# Zio_4_DC_Motor_Controller.net
KiCad netlist of a schematic drawn in EAGLE
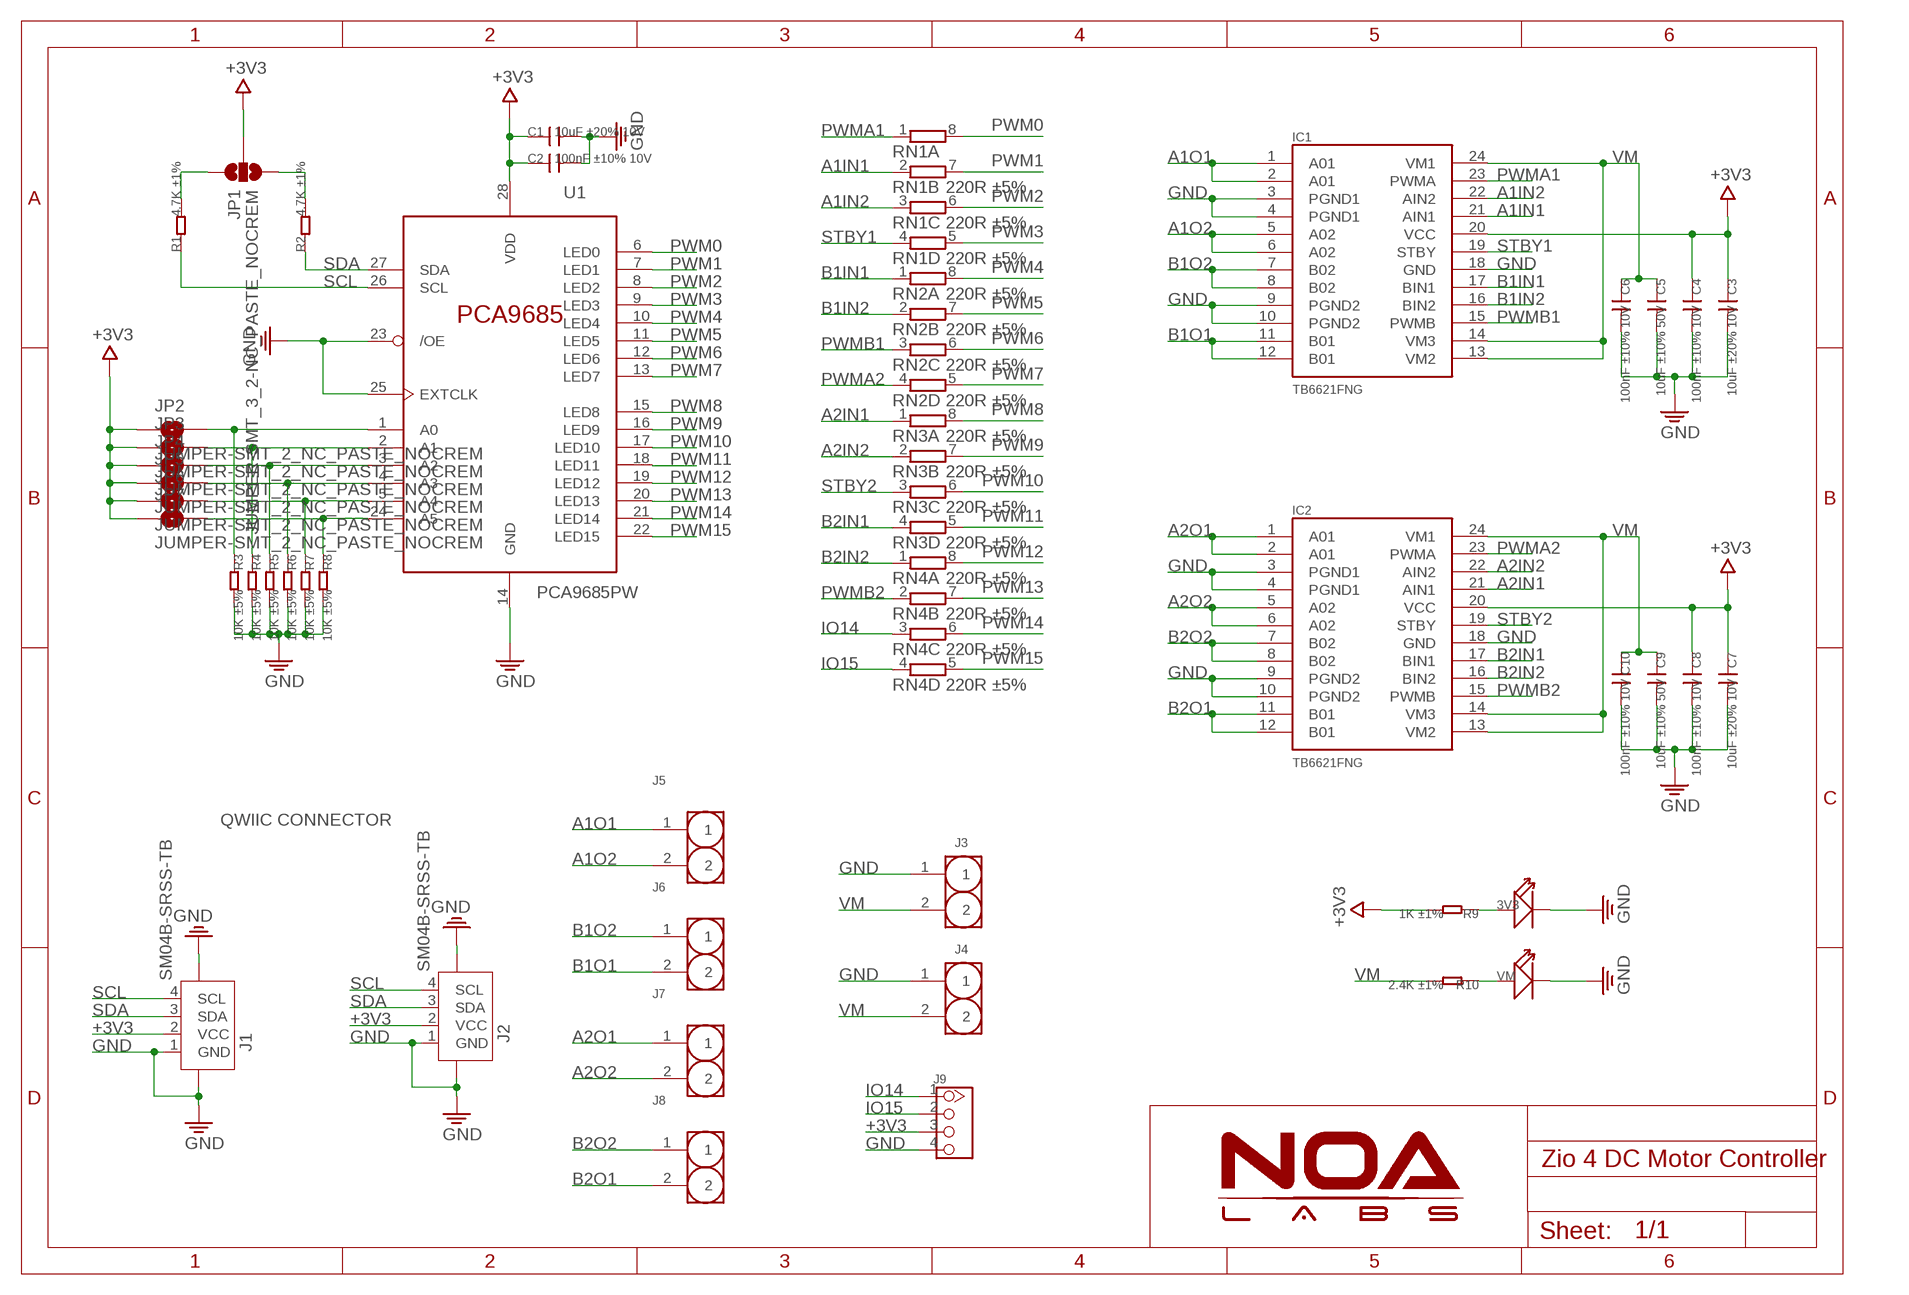
[diagram p0: schematic, sheet 1]

(export (version "E")
  (design (tool "Eeschema 10.0.6"))
  (components
    (comp (ref "3V3")
      (value "LED'0805'")
      (footprint "eagle-import:LED-0805")
      (libsource (lib "eagle-import") (part "LED'0805'"))
    )
    (comp (ref "C1")
      (value "10uF ±20% 10V")
      (footprint "eagle-import:0603")
      (libsource (lib "eagle-import") (part "C-0603"))
    )
    (comp (ref "C2")
      (value "100nF ±10% 10V")
      (footprint "eagle-import:0603")
      (libsource (lib "eagle-import") (part "C-0603"))
    )
    (comp (ref "C3")
      (value "10uF ±20% 10V")
      (footprint "eagle-import:0603")
      (libsource (lib "eagle-import") (part "C-0603"))
    )
    (comp (ref "C4")
      (value "100nF ±10% 10V")
      (footprint "eagle-import:0603")
      (libsource (lib "eagle-import") (part "C-0603"))
    )
    (comp (ref "C5")
      (value "10uF ±10% 50V")
      (footprint "eagle-import:0805")
      (libsource (lib "eagle-import") (part "C-0805"))
    )
    (comp (ref "C6")
      (value "100nF ±10% 10V")
      (footprint "eagle-import:0603")
      (libsource (lib "eagle-import") (part "C-0603"))
    )
    (comp (ref "C7")
      (value "10uF ±20% 10V")
      (footprint "eagle-import:0603")
      (libsource (lib "eagle-import") (part "C-0603"))
    )
    (comp (ref "C8")
      (value "100nF ±10% 10V")
      (footprint "eagle-import:0603")
      (libsource (lib "eagle-import") (part "C-0603"))
    )
    (comp (ref "C9")
      (value "10uF ±10% 50V")
      (footprint "eagle-import:0805")
      (libsource (lib "eagle-import") (part "C-0805"))
    )
    (comp (ref "C10")
      (value "100nF ±10% 10V")
      (footprint "eagle-import:0603")
      (libsource (lib "eagle-import") (part "C-0603"))
    )
    (comp (ref "IC1")
      (value "TB6621FNG")
      (footprint "eagle-import:SSOP24")
      (libsource (lib "eagle-import") (part "TB6621FNG"))
    )
    (comp (ref "IC2")
      (value "TB6621FNG")
      (footprint "eagle-import:SSOP24")
      (libsource (lib "eagle-import") (part "TB6621FNG"))
    )
    (comp (ref "J1")
      (value "SM04B-SRSS-TB")
      (footprint "eagle-import:JST-SH-4P")
      (libsource (lib "eagle-import") (part "JST-SH-4P-1.0"))
    )
    (comp (ref "J2")
      (value "SM04B-SRSS-TB")
      (footprint "eagle-import:JST-SH-4P")
      (libsource (lib "eagle-import") (part "JST-SH-4P-1.0"))
    )
    (comp (ref "J3")
      (value "HEADER-2P-2.0-90")
      (footprint "eagle-import:PH2.0-2P-90")
      (libsource (lib "eagle-import") (part "HEADER-2P-2.0-90"))
    )
    (comp (ref "J4")
      (value "HEADER-2P-2.0-90")
      (footprint "eagle-import:PH2.0-2P-90")
      (libsource (lib "eagle-import") (part "HEADER-2P-2.0-90"))
    )
    (comp (ref "J5")
      (value "HEADER-2P-SCREW5.0")
      (footprint "eagle-import:2P-SCREW-5.0")
      (libsource (lib "eagle-import") (part "HEADER-2P-SCREW5.0"))
    )
    (comp (ref "J6")
      (value "HEADER-2P-SCREW5.0")
      (footprint "eagle-import:2P-SCREW-5.0")
      (libsource (lib "eagle-import") (part "HEADER-2P-SCREW5.0"))
    )
    (comp (ref "J7")
      (value "HEADER-2P-SCREW5.0")
      (footprint "eagle-import:2P-SCREW-5.0")
      (libsource (lib "eagle-import") (part "HEADER-2P-SCREW5.0"))
    )
    (comp (ref "J8")
      (value "HEADER-2P-SCREW5.0")
      (footprint "eagle-import:2P-SCREW-5.0")
      (libsource (lib "eagle-import") (part "HEADER-2P-SCREW5.0"))
    )
    (comp (ref "J9")
      (value "HEADER-4P-80/40MIL")
      (footprint "eagle-import:4P-2.54-80_40MIL")
      (libsource (lib "eagle-import") (part "HEADER-4P-80/40MIL"))
    )
    (comp (ref "JP1")
      (value "JUMPER-SMT_3_2-NC_PASTE_NOCREM")
      (footprint "eagle-import:SMT-JUMPER_3_2-NC_PASTE_SILK_NOCREM")
      (libsource (lib "eagle-import") (part "JUMPER-SMT_3_2-NC_PASTE_NOCREM"))
    )
    (comp (ref "JP2")
      (value "JUMPER-SMT_2_NC_PASTE_NOCREM")
      (footprint "eagle-import:SMT-JUMPER_2_NC_PASTE_SILK_NOCREM")
      (libsource (lib "eagle-import") (part "JUMPER-SMT_2_NC_PASTE_NOCREM"))
    )
    (comp (ref "JP3")
      (value "JUMPER-SMT_2_NC_PASTE_NOCREM")
      (footprint "eagle-import:SMT-JUMPER_2_NC_PASTE_SILK_NOCREM")
      (libsource (lib "eagle-import") (part "JUMPER-SMT_2_NC_PASTE_NOCREM"))
    )
    (comp (ref "JP4")
      (value "JUMPER-SMT_2_NC_PASTE_NOCREM")
      (footprint "eagle-import:SMT-JUMPER_2_NC_PASTE_SILK_NOCREM")
      (libsource (lib "eagle-import") (part "JUMPER-SMT_2_NC_PASTE_NOCREM"))
    )
    (comp (ref "JP5")
      (value "JUMPER-SMT_2_NC_PASTE_NOCREM")
      (footprint "eagle-import:SMT-JUMPER_2_NC_PASTE_SILK_NOCREM")
      (libsource (lib "eagle-import") (part "JUMPER-SMT_2_NC_PASTE_NOCREM"))
    )
    (comp (ref "JP6")
      (value "JUMPER-SMT_2_NC_PASTE_NOCREM")
      (footprint "eagle-import:SMT-JUMPER_2_NC_PASTE_SILK_NOCREM")
      (libsource (lib "eagle-import") (part "JUMPER-SMT_2_NC_PASTE_NOCREM"))
    )
    (comp (ref "JP7")
      (value "JUMPER-SMT_2_NC_PASTE_NOCREM")
      (footprint "eagle-import:SMT-JUMPER_2_NC_PASTE_SILK_NOCREM")
      (libsource (lib "eagle-import") (part "JUMPER-SMT_2_NC_PASTE_NOCREM"))
    )
    (comp (ref "R1")
      (value "4.7K ±1%")
      (footprint "eagle-import:0603")
      (libsource (lib "eagle-import") (part "Discretex_R-0603"))
    )
    (comp (ref "R2")
      (value "4.7K ±1%")
      (footprint "eagle-import:0603")
      (libsource (lib "eagle-import") (part "Discretex_R-0603"))
    )
    (comp (ref "R3")
      (value "10K ±5%")
      (footprint "eagle-import:0402")
      (libsource (lib "eagle-import") (part "R-0402"))
    )
    (comp (ref "R4")
      (value "10K ±5%")
      (footprint "eagle-import:0402")
      (libsource (lib "eagle-import") (part "R-0402"))
    )
    (comp (ref "R5")
      (value "10K ±5%")
      (footprint "eagle-import:0402")
      (libsource (lib "eagle-import") (part "R-0402"))
    )
    (comp (ref "R6")
      (value "10K ±5%")
      (footprint "eagle-import:0402")
      (libsource (lib "eagle-import") (part "R-0402"))
    )
    (comp (ref "R7")
      (value "10K ±5%")
      (footprint "eagle-import:0402")
      (libsource (lib "eagle-import") (part "R-0402"))
    )
    (comp (ref "R8")
      (value "10K ±5%")
      (footprint "eagle-import:0402")
      (libsource (lib "eagle-import") (part "R-0402"))
    )
    (comp (ref "R9")
      (value "1K ±1%")
      (footprint "eagle-import:0603")
      (libsource (lib "eagle-import") (part "Discretex_R-0603"))
    )
    (comp (ref "R10")
      (value "2.4K ±1%")
      (footprint "eagle-import:0603")
      (libsource (lib "eagle-import") (part "Discretex_R-0603"))
    )
    (comp (ref "RN1")
      (value "220R ±5%")
      (footprint "eagle-import:RESISTOR-DIL_0603-ARV")
      (libsource (lib "eagle-import") (part "RESISTOR-DIL_4R-N0603-ARV"))
    )
    (comp (ref "RN2")
      (value "220R ±5%")
      (footprint "eagle-import:RESISTOR-DIL_0603-ARV")
      (libsource (lib "eagle-import") (part "RESISTOR-DIL_4R-N0603-ARV"))
    )
    (comp (ref "RN3")
      (value "220R ±5%")
      (footprint "eagle-import:RESISTOR-DIL_0603-ARV")
      (libsource (lib "eagle-import") (part "RESISTOR-DIL_4R-N0603-ARV"))
    )
    (comp (ref "RN4")
      (value "220R ±5%")
      (footprint "eagle-import:RESISTOR-DIL_0603-ARV")
      (libsource (lib "eagle-import") (part "RESISTOR-DIL_4R-N0603-ARV"))
    )
    (comp (ref "U1")
      (value "PCA9685PW")
      (footprint "eagle-import:TSSOP28")
      (libsource (lib "eagle-import") (part "PCA9685PW"))
    )
    (comp (ref "VM")
      (value "LED'0805'")
      (footprint "eagle-import:LED-0805")
      (libsource (lib "eagle-import") (part "LED'0805'"))
    )
  )
  (nets
    (net (code "1") (name "+3V3") (class "Default")
      (node (ref "C1") (pin "1") (pinfunction "1_1") (pintype "passive"))
      (node (ref "C2") (pin "1") (pinfunction "1_1") (pintype "passive"))
      (node (ref "C3") (pin "1") (pinfunction "1_1") (pintype "passive"))
      (node (ref "C4") (pin "1") (pinfunction "1_1") (pintype "passive"))
      (node (ref "C7") (pin "1") (pinfunction "1_1") (pintype "passive"))
      (node (ref "C8") (pin "1") (pinfunction "1_1") (pintype "passive"))
      (node (ref "IC1") (pin "20") (pinfunction "VCC_20") (pintype "bidirectional"))
      (node (ref "IC2") (pin "20") (pinfunction "VCC_20") (pintype "bidirectional"))
      (node (ref "J1") (pin "2") (pinfunction "VCC_2") (pintype "bidirectional"))
      (node (ref "J2") (pin "2") (pinfunction "VCC_2") (pintype "bidirectional"))
      (node (ref "J9") (pin "3") (pinfunction "P$3_3") (pintype "bidirectional"))
      (node (ref "JP1") (pin "2") (pinfunction "2_2") (pintype "passive"))
      (node (ref "JP2") (pin "1") (pinfunction "1_1") (pintype "passive"))
      (node (ref "JP3") (pin "1") (pinfunction "1_1") (pintype "passive"))
      (node (ref "JP4") (pin "1") (pinfunction "1_1") (pintype "passive"))
      (node (ref "JP5") (pin "1") (pinfunction "1_1") (pintype "passive"))
      (node (ref "JP6") (pin "1") (pinfunction "1_1") (pintype "passive"))
      (node (ref "JP7") (pin "1") (pinfunction "1_1") (pintype "passive"))
      (node (ref "R9") (pin "2") (pinfunction "2_2") (pintype "passive"))
      (node (ref "U1") (pin "28") (pinfunction "VDD_28") (pintype "power_in"))
    )
    (net (code "2") (name "/A1IN1") (class "Default")
      (node (ref "IC1") (pin "21") (pinfunction "AIN1_21") (pintype "bidirectional"))
      (node (ref "RN1") (pin "2") (pinfunction "1_2") (pintype "passive"))
    )
    (net (code "3") (name "/A1IN2") (class "Default")
      (node (ref "IC1") (pin "22") (pinfunction "AIN2_22") (pintype "bidirectional"))
      (node (ref "RN1") (pin "3") (pinfunction "1_3") (pintype "passive"))
    )
    (net (code "4") (name "/A1O1") (class "Default")
      (node (ref "IC1") (pin "1") (pinfunction "A01_1") (pintype "bidirectional"))
      (node (ref "IC1") (pin "2") (pinfunction "A01_2") (pintype "bidirectional"))
      (node (ref "J5") (pin "1") (pinfunction "1_1") (pintype "bidirectional"))
    )
    (net (code "5") (name "/A1O2") (class "Default")
      (node (ref "IC1") (pin "5") (pinfunction "A02_5") (pintype "bidirectional"))
      (node (ref "IC1") (pin "6") (pinfunction "A02_6") (pintype "bidirectional"))
      (node (ref "J5") (pin "2") (pinfunction "2_2") (pintype "bidirectional"))
    )
    (net (code "6") (name "/A2IN1") (class "Default")
      (node (ref "IC2") (pin "21") (pinfunction "AIN1_21") (pintype "bidirectional"))
      (node (ref "RN3") (pin "1") (pinfunction "1_1") (pintype "passive"))
    )
    (net (code "7") (name "/A2IN2") (class "Default")
      (node (ref "IC2") (pin "22") (pinfunction "AIN2_22") (pintype "bidirectional"))
      (node (ref "RN3") (pin "2") (pinfunction "1_2") (pintype "passive"))
    )
    (net (code "8") (name "/A2O1") (class "Default")
      (node (ref "IC2") (pin "1") (pinfunction "A01_1") (pintype "bidirectional"))
      (node (ref "IC2") (pin "2") (pinfunction "A01_2") (pintype "bidirectional"))
      (node (ref "J7") (pin "1") (pinfunction "1_1") (pintype "bidirectional"))
    )
    (net (code "9") (name "/A2O2") (class "Default")
      (node (ref "IC2") (pin "5") (pinfunction "A02_5") (pintype "bidirectional"))
      (node (ref "IC2") (pin "6") (pinfunction "A02_6") (pintype "bidirectional"))
      (node (ref "J7") (pin "2") (pinfunction "2_2") (pintype "bidirectional"))
    )
    (net (code "10") (name "/B1IN1") (class "Default")
      (node (ref "IC1") (pin "17") (pinfunction "BIN1_17") (pintype "bidirectional"))
      (node (ref "RN2") (pin "1") (pinfunction "1_1") (pintype "passive"))
    )
    (net (code "11") (name "/B1IN2") (class "Default")
      (node (ref "IC1") (pin "16") (pinfunction "BIN2_16") (pintype "bidirectional"))
      (node (ref "RN2") (pin "2") (pinfunction "1_2") (pintype "passive"))
    )
    (net (code "12") (name "/B1O1") (class "Default")
      (node (ref "IC1") (pin "11") (pinfunction "B01_11") (pintype "bidirectional"))
      (node (ref "IC1") (pin "12") (pinfunction "B01_12") (pintype "bidirectional"))
      (node (ref "J6") (pin "2") (pinfunction "2_2") (pintype "bidirectional"))
    )
    (net (code "13") (name "/B1O2") (class "Default")
      (node (ref "IC1") (pin "7") (pinfunction "B02_7") (pintype "bidirectional"))
      (node (ref "IC1") (pin "8") (pinfunction "B02_8") (pintype "bidirectional"))
      (node (ref "J6") (pin "1") (pinfunction "1_1") (pintype "bidirectional"))
    )
    (net (code "14") (name "/B2IN1") (class "Default")
      (node (ref "IC2") (pin "17") (pinfunction "BIN1_17") (pintype "bidirectional"))
      (node (ref "RN3") (pin "4") (pinfunction "1_4") (pintype "passive"))
    )
    (net (code "15") (name "/B2IN2") (class "Default")
      (node (ref "IC2") (pin "16") (pinfunction "BIN2_16") (pintype "bidirectional"))
      (node (ref "RN4") (pin "1") (pinfunction "1_1") (pintype "passive"))
    )
    (net (code "16") (name "/B2O1") (class "Default")
      (node (ref "IC2") (pin "11") (pinfunction "B01_11") (pintype "bidirectional"))
      (node (ref "IC2") (pin "12") (pinfunction "B01_12") (pintype "bidirectional"))
      (node (ref "J8") (pin "2") (pinfunction "2_2") (pintype "bidirectional"))
    )
    (net (code "17") (name "/B2O2") (class "Default")
      (node (ref "IC2") (pin "7") (pinfunction "B02_7") (pintype "bidirectional"))
      (node (ref "IC2") (pin "8") (pinfunction "B02_8") (pintype "bidirectional"))
      (node (ref "J8") (pin "1") (pinfunction "1_1") (pintype "bidirectional"))
    )
    (net (code "18") (name "/IO14") (class "Default")
      (node (ref "J9") (pin "1") (pinfunction "P$1_1") (pintype "bidirectional"))
      (node (ref "RN4") (pin "3") (pinfunction "1_3") (pintype "passive"))
    )
    (net (code "19") (name "/IO15") (class "Default")
      (node (ref "J9") (pin "2") (pinfunction "P$2_2") (pintype "bidirectional"))
      (node (ref "RN4") (pin "4") (pinfunction "1_4") (pintype "passive"))
    )
    (net (code "20") (name "/PWM0") (class "Default")
      (node (ref "RN1") (pin "8") (pinfunction "2_8") (pintype "passive"))
      (node (ref "U1") (pin "6") (pinfunction "LED0_6") (pintype "bidirectional"))
    )
    (net (code "21") (name "/PWM1") (class "Default")
      (node (ref "RN1") (pin "7") (pinfunction "2_7") (pintype "passive"))
      (node (ref "U1") (pin "7") (pinfunction "LED1_7") (pintype "bidirectional"))
    )
    (net (code "22") (name "/PWM2") (class "Default")
      (node (ref "RN1") (pin "6") (pinfunction "2_6") (pintype "passive"))
      (node (ref "U1") (pin "8") (pinfunction "LED2_8") (pintype "bidirectional"))
    )
    (net (code "23") (name "/PWM3") (class "Default")
      (node (ref "RN1") (pin "5") (pinfunction "2_5") (pintype "passive"))
      (node (ref "U1") (pin "9") (pinfunction "LED3_9") (pintype "bidirectional"))
    )
    (net (code "24") (name "/PWM4") (class "Default")
      (node (ref "RN2") (pin "8") (pinfunction "2_8") (pintype "passive"))
      (node (ref "U1") (pin "10") (pinfunction "LED4_10") (pintype "bidirectional"))
    )
    (net (code "25") (name "/PWM5") (class "Default")
      (node (ref "RN2") (pin "7") (pinfunction "2_7") (pintype "passive"))
      (node (ref "U1") (pin "11") (pinfunction "LED5_11") (pintype "bidirectional"))
    )
    (net (code "26") (name "/PWM6") (class "Default")
      (node (ref "RN2") (pin "6") (pinfunction "2_6") (pintype "passive"))
      (node (ref "U1") (pin "12") (pinfunction "LED6_12") (pintype "bidirectional"))
    )
    (net (code "27") (name "/PWM7") (class "Default")
      (node (ref "RN2") (pin "5") (pinfunction "2_5") (pintype "passive"))
      (node (ref "U1") (pin "13") (pinfunction "LED7_13") (pintype "bidirectional"))
    )
    (net (code "28") (name "/PWM8") (class "Default")
      (node (ref "RN3") (pin "8") (pinfunction "2_8") (pintype "passive"))
      (node (ref "U1") (pin "15") (pinfunction "LED8_15") (pintype "bidirectional"))
    )
    (net (code "29") (name "/PWM9") (class "Default")
      (node (ref "RN3") (pin "7") (pinfunction "2_7") (pintype "passive"))
      (node (ref "U1") (pin "16") (pinfunction "LED9_16") (pintype "bidirectional"))
    )
    (net (code "30") (name "/PWM10") (class "Default")
      (node (ref "RN3") (pin "6") (pinfunction "2_6") (pintype "passive"))
      (node (ref "U1") (pin "17") (pinfunction "LED10_17") (pintype "bidirectional"))
    )
    (net (code "31") (name "/PWM11") (class "Default")
      (node (ref "RN3") (pin "5") (pinfunction "2_5") (pintype "passive"))
      (node (ref "U1") (pin "18") (pinfunction "LED11_18") (pintype "bidirectional"))
    )
    (net (code "32") (name "/PWM12") (class "Default")
      (node (ref "RN4") (pin "8") (pinfunction "2_8") (pintype "passive"))
      (node (ref "U1") (pin "19") (pinfunction "LED12_19") (pintype "bidirectional"))
    )
    (net (code "33") (name "/PWM13") (class "Default")
      (node (ref "RN4") (pin "7") (pinfunction "2_7") (pintype "passive"))
      (node (ref "U1") (pin "20") (pinfunction "LED13_20") (pintype "bidirectional"))
    )
    (net (code "34") (name "/PWM14") (class "Default")
      (node (ref "RN4") (pin "6") (pinfunction "2_6") (pintype "passive"))
      (node (ref "U1") (pin "21") (pinfunction "LED14_21") (pintype "bidirectional"))
    )
    (net (code "35") (name "/PWM15") (class "Default")
      (node (ref "RN4") (pin "5") (pinfunction "2_5") (pintype "passive"))
      (node (ref "U1") (pin "22") (pinfunction "LED15_22") (pintype "bidirectional"))
    )
    (net (code "36") (name "/PWMA1") (class "Default")
      (node (ref "IC1") (pin "23") (pinfunction "PWMA_23") (pintype "bidirectional"))
      (node (ref "RN1") (pin "1") (pinfunction "1_1") (pintype "passive"))
    )
    (net (code "37") (name "/PWMA2") (class "Default")
      (node (ref "IC2") (pin "23") (pinfunction "PWMA_23") (pintype "bidirectional"))
      (node (ref "RN2") (pin "4") (pinfunction "1_4") (pintype "passive"))
    )
    (net (code "38") (name "/PWMB1") (class "Default")
      (node (ref "IC1") (pin "15") (pinfunction "PWMB_15") (pintype "bidirectional"))
      (node (ref "RN2") (pin "3") (pinfunction "1_3") (pintype "passive"))
    )
    (net (code "39") (name "/PWMB2") (class "Default")
      (node (ref "IC2") (pin "15") (pinfunction "PWMB_15") (pintype "bidirectional"))
      (node (ref "RN4") (pin "2") (pinfunction "1_2") (pintype "passive"))
    )
    (net (code "40") (name "/SCL") (class "Default")
      (node (ref "J1") (pin "4") (pinfunction "SCL_4") (pintype "bidirectional"))
      (node (ref "J2") (pin "4") (pinfunction "SCL_4") (pintype "bidirectional"))
      (node (ref "R1") (pin "1") (pinfunction "1_1") (pintype "passive"))
      (node (ref "U1") (pin "26") (pinfunction "SCL_26") (pintype "bidirectional"))
    )
    (net (code "41") (name "/SDA") (class "Default")
      (node (ref "J1") (pin "3") (pinfunction "SDA_3") (pintype "bidirectional"))
      (node (ref "J2") (pin "3") (pinfunction "SDA_3") (pintype "bidirectional"))
      (node (ref "R2") (pin "1") (pinfunction "1_1") (pintype "passive"))
      (node (ref "U1") (pin "27") (pinfunction "SDA_27") (pintype "bidirectional"))
    )
    (net (code "42") (name "/STBY1") (class "Default")
      (node (ref "IC1") (pin "19") (pinfunction "STBY_19") (pintype "bidirectional"))
      (node (ref "RN1") (pin "4") (pinfunction "1_4") (pintype "passive"))
    )
    (net (code "43") (name "/STBY2") (class "Default")
      (node (ref "IC2") (pin "19") (pinfunction "STBY_19") (pintype "bidirectional"))
      (node (ref "RN3") (pin "3") (pinfunction "1_3") (pintype "passive"))
    )
    (net (code "44") (name "/VM") (class "Default")
      (node (ref "C10") (pin "1") (pinfunction "1_1") (pintype "passive"))
      (node (ref "C5") (pin "1") (pinfunction "1_1") (pintype "passive"))
      (node (ref "C6") (pin "1") (pinfunction "1_1") (pintype "passive"))
      (node (ref "C9") (pin "1") (pinfunction "1_1") (pintype "passive"))
      (node (ref "IC1") (pin "13") (pinfunction "VM2_13") (pintype "bidirectional"))
      (node (ref "IC1") (pin "14") (pinfunction "VM3_14") (pintype "bidirectional"))
      (node (ref "IC1") (pin "24") (pinfunction "VM1_24") (pintype "bidirectional"))
      (node (ref "IC2") (pin "13") (pinfunction "VM2_13") (pintype "bidirectional"))
      (node (ref "IC2") (pin "14") (pinfunction "VM3_14") (pintype "bidirectional"))
      (node (ref "IC2") (pin "24") (pinfunction "VM1_24") (pintype "bidirectional"))
      (node (ref "J3") (pin "2") (pinfunction "2_2") (pintype "bidirectional"))
      (node (ref "J4") (pin "2") (pinfunction "2_2") (pintype "bidirectional"))
      (node (ref "R10") (pin "2") (pinfunction "2_2") (pintype "passive"))
    )
    (net (code "45") (name "GND") (class "Default")
      (node (ref "3V3") (pin "-") (pinfunction "-_-") (pintype "passive"))
      (node (ref "C1") (pin "2") (pinfunction "2_2") (pintype "passive"))
      (node (ref "C10") (pin "2") (pinfunction "2_2") (pintype "passive"))
      (node (ref "C2") (pin "2") (pinfunction "2_2") (pintype "passive"))
      (node (ref "C3") (pin "2") (pinfunction "2_2") (pintype "passive"))
      (node (ref "C4") (pin "2") (pinfunction "2_2") (pintype "passive"))
      (node (ref "C5") (pin "2") (pinfunction "2_2") (pintype "passive"))
      (node (ref "C6") (pin "2") (pinfunction "2_2") (pintype "passive"))
      (node (ref "C7") (pin "2") (pinfunction "2_2") (pintype "passive"))
      (node (ref "C8") (pin "2") (pinfunction "2_2") (pintype "passive"))
      (node (ref "C9") (pin "2") (pinfunction "2_2") (pintype "passive"))
      (node (ref "IC1") (pin "10") (pinfunction "PGND2_10") (pintype "bidirectional"))
      (node (ref "IC1") (pin "18") (pinfunction "GND_18") (pintype "bidirectional"))
      (node (ref "IC1") (pin "3") (pinfunction "PGND1_3") (pintype "bidirectional"))
      (node (ref "IC1") (pin "4") (pinfunction "PGND1_4") (pintype "bidirectional"))
      (node (ref "IC1") (pin "9") (pinfunction "PGND2_9") (pintype "bidirectional"))
      (node (ref "IC2") (pin "10") (pinfunction "PGND2_10") (pintype "bidirectional"))
      (node (ref "IC2") (pin "18") (pinfunction "GND_18") (pintype "bidirectional"))
      (node (ref "IC2") (pin "3") (pinfunction "PGND1_3") (pintype "bidirectional"))
      (node (ref "IC2") (pin "4") (pinfunction "PGND1_4") (pintype "bidirectional"))
      (node (ref "IC2") (pin "9") (pinfunction "PGND2_9") (pintype "bidirectional"))
      (node (ref "J1") (pin "1") (pinfunction "GND_1") (pintype "bidirectional"))
      (node (ref "J1") (pin "NC1") (pinfunction "5_NC1") (pintype "bidirectional"))
      (node (ref "J1") (pin "NC2") (pinfunction "6_NC2") (pintype "bidirectional"))
      (node (ref "J2") (pin "1") (pinfunction "GND_1") (pintype "bidirectional"))
      (node (ref "J2") (pin "NC1") (pinfunction "5_NC1") (pintype "bidirectional"))
      (node (ref "J2") (pin "NC2") (pinfunction "6_NC2") (pintype "bidirectional"))
      (node (ref "J3") (pin "1") (pinfunction "1_1") (pintype "bidirectional"))
      (node (ref "J4") (pin "1") (pinfunction "1_1") (pintype "bidirectional"))
      (node (ref "J9") (pin "4") (pinfunction "P$4_4") (pintype "bidirectional"))
      (node (ref "R3") (pin "2") (pinfunction "2_2") (pintype "passive"))
      (node (ref "R4") (pin "2") (pinfunction "2_2") (pintype "passive"))
      (node (ref "R5") (pin "2") (pinfunction "2_2") (pintype "passive"))
      (node (ref "R6") (pin "2") (pinfunction "2_2") (pintype "passive"))
      (node (ref "R7") (pin "2") (pinfunction "2_2") (pintype "passive"))
      (node (ref "R8") (pin "2") (pinfunction "2_2") (pintype "passive"))
      (node (ref "U1") (pin "14") (pinfunction "GND_14") (pintype "power_in"))
      (node (ref "U1") (pin "23") (pinfunction "/OE_23") (pintype "bidirectional"))
      (node (ref "U1") (pin "25") (pinfunction "EXTCLK_25") (pintype "input"))
      (node (ref "VM") (pin "-") (pinfunction "-_-") (pintype "passive"))
    )
    (net (code "46") (name "Net-(3V3-Pad+)") (class "Default")
      (node (ref "3V3") (pin "+") (pinfunction "+_+") (pintype "passive"))
      (node (ref "R9") (pin "1") (pinfunction "1_1") (pintype "passive"))
    )
    (net (code "47") (name "Net-(JP1-Pad1)") (class "Default")
      (node (ref "JP1") (pin "1") (pinfunction "1_1") (pintype "passive"))
      (node (ref "R1") (pin "2") (pinfunction "2_2") (pintype "passive"))
    )
    (net (code "48") (name "Net-(JP1-Pad3)") (class "Default")
      (node (ref "JP1") (pin "3") (pinfunction "3_3") (pintype "passive"))
      (node (ref "R2") (pin "2") (pinfunction "2_2") (pintype "passive"))
    )
    (net (code "49") (name "Net-(R10-Pad1)") (class "Default")
      (node (ref "R10") (pin "1") (pinfunction "1_1") (pintype "passive"))
      (node (ref "VM") (pin "+") (pinfunction "+_+") (pintype "passive"))
    )
    (net (code "50") (name "Net-(U1-A0)") (class "Default")
      (node (ref "JP2") (pin "2") (pinfunction "2_2") (pintype "passive"))
      (node (ref "R3") (pin "1") (pinfunction "1_1") (pintype "passive"))
      (node (ref "U1") (pin "1") (pinfunction "A0_1") (pintype "bidirectional"))
    )
    (net (code "51") (name "Net-(U1-A1)") (class "Default")
      (node (ref "JP3") (pin "2") (pinfunction "2_2") (pintype "passive"))
      (node (ref "R4") (pin "1") (pinfunction "1_1") (pintype "passive"))
      (node (ref "U1") (pin "2") (pinfunction "A1_2") (pintype "bidirectional"))
    )
    (net (code "52") (name "Net-(U1-A2)") (class "Default")
      (node (ref "JP4") (pin "2") (pinfunction "2_2") (pintype "passive"))
      (node (ref "R5") (pin "1") (pinfunction "1_1") (pintype "passive"))
      (node (ref "U1") (pin "3") (pinfunction "A2_3") (pintype "bidirectional"))
    )
    (net (code "53") (name "Net-(U1-A3)") (class "Default")
      (node (ref "JP5") (pin "2") (pinfunction "2_2") (pintype "passive"))
      (node (ref "R6") (pin "1") (pinfunction "1_1") (pintype "passive"))
      (node (ref "U1") (pin "4") (pinfunction "A3_4") (pintype "bidirectional"))
    )
    (net (code "54") (name "Net-(U1-A4)") (class "Default")
      (node (ref "JP6") (pin "2") (pinfunction "2_2") (pintype "passive"))
      (node (ref "R7") (pin "1") (pinfunction "1_1") (pintype "passive"))
      (node (ref "U1") (pin "5") (pinfunction "A4_5") (pintype "bidirectional"))
    )
    (net (code "55") (name "Net-(U1-A5)") (class "Default")
      (node (ref "JP7") (pin "2") (pinfunction "2_2") (pintype "passive"))
      (node (ref "R8") (pin "1") (pinfunction "1_1") (pintype "passive"))
      (node (ref "U1") (pin "24") (pinfunction "A5_24") (pintype "bidirectional"))
    )
  )
)
